# breakout_ina169.net
KiCad netlist of a schematic drawn in EAGLE
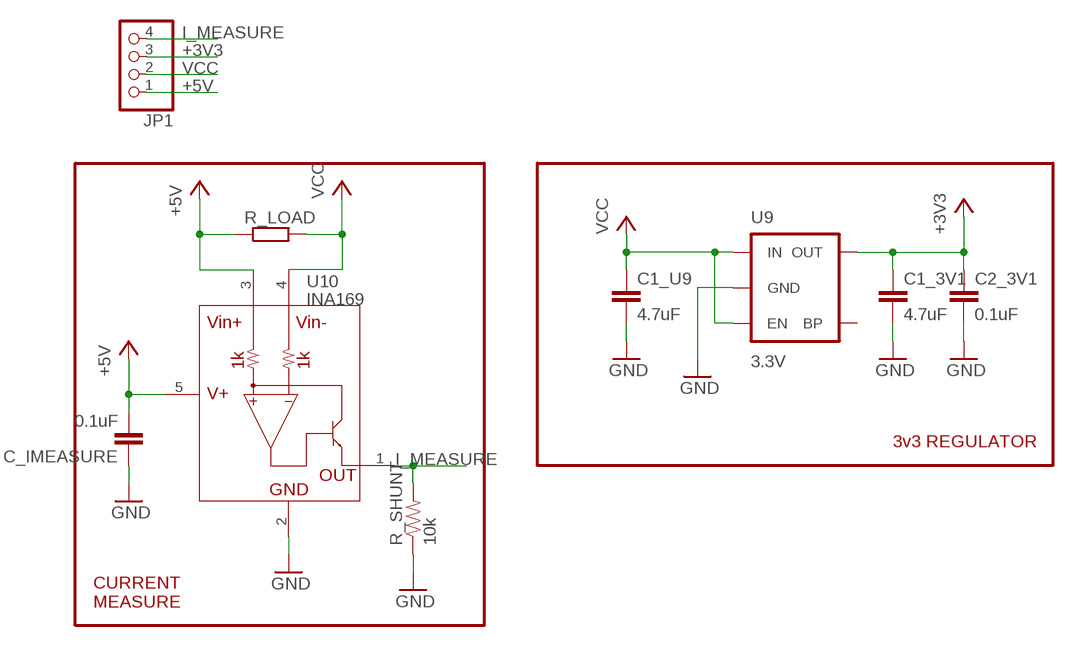
[diagram p0: schematic, sheet 1]

(export (version "E")
  (design (tool "Eeschema 10.0.6"))
  (components
    (comp (ref "C1_3V1")
      (value "4.7uF")
      (footprint "eagle-import:0402-CAP")
      (libsource (lib "eagle-import") (part "CAP0402-CAP"))
    )
    (comp (ref "C1_U9")
      (value "4.7uF")
      (footprint "eagle-import:0402-CAP")
      (libsource (lib "eagle-import") (part "CAP0402-CAP"))
    )
    (comp (ref "C2_3V1")
      (value "0.1uF")
      (footprint "eagle-import:0402-CAP")
      (libsource (lib "eagle-import") (part "CAP0402-CAP"))
    )
    (comp (ref "C_IMEASURE")
      (value "0.1uF")
      (footprint "eagle-import:0603-CAP")
      (libsource (lib "eagle-import") (part "SparkFun-Passives_CAP0603-CAP"))
    )
    (comp (ref "JP1")
      (value "PINHD-1X4")
      (footprint "eagle-import:1X04")
      (libsource (lib "eagle-import") (part "PINHD-1X4"))
    )
    (comp (ref "R_LOAD")
      (value "R-EU_0309/10")
      (footprint "eagle-import:0309_10")
      (fields (field (name "SIZE") "1206") (field (name "TOL") "1%"))
      (libsource (lib "eagle-import") (part "R-EU_0309/10"))
    )
    (comp (ref "R_SHUNT")
      (value "10k")
      (footprint "eagle-import:0603-RES")
      (fields (field (name "TOL") "1%"))
      (libsource (lib "eagle-import") (part "RESISTOR0603"))
    )
    (comp (ref "U9")
      (value "3.3V")
      (footprint "eagle-import:SOT23-5")
      (libsource (lib "eagle-import") (part "V_REG_LDOSMD"))
    )
    (comp (ref "U10")
      (value "INA169")
      (footprint "eagle-import:SOT23-5")
      (libsource (lib "eagle-import") (part "INA169"))
    )
  )
  (nets
    (net (code "1") (name "+3V3") (class "Default")
      (node (ref "C1_3V1") (pin "1") (pinfunction "1_1") (pintype "passive"))
      (node (ref "C2_3V1") (pin "1") (pinfunction "1_1") (pintype "passive"))
      (node (ref "JP1") (pin "3") (pinfunction "3_3") (pintype "passive"))
      (node (ref "U9") (pin "5") (pinfunction "OUT_5") (pintype "passive"))
    )
    (net (code "2") (name "+5V") (class "Default")
      (node (ref "C_IMEASURE") (pin "2") (pinfunction "2_2") (pintype "passive"))
      (node (ref "JP1") (pin "1") (pinfunction "1_1") (pintype "passive"))
      (node (ref "R_LOAD") (pin "1") (pinfunction "1_1") (pintype "passive"))
      (node (ref "U10") (pin "3") (pinfunction "VIN+_3") (pintype "bidirectional"))
      (node (ref "U10") (pin "5") (pinfunction "V+_5") (pintype "bidirectional"))
    )
    (net (code "3") (name "/I_MEASURE") (class "Default")
      (node (ref "JP1") (pin "4") (pinfunction "4_4") (pintype "passive"))
      (node (ref "R_SHUNT") (pin "2") (pinfunction "2_2") (pintype "passive"))
      (node (ref "U10") (pin "1") (pinfunction "OUT_1") (pintype "bidirectional"))
    )
    (net (code "4") (name "GND") (class "Default")
      (node (ref "C1_3V1") (pin "2") (pinfunction "2_2") (pintype "passive"))
      (node (ref "C1_U9") (pin "2") (pinfunction "2_2") (pintype "passive"))
      (node (ref "C2_3V1") (pin "2") (pinfunction "2_2") (pintype "passive"))
      (node (ref "C_IMEASURE") (pin "1") (pinfunction "1_1") (pintype "passive"))
      (node (ref "R_SHUNT") (pin "1") (pinfunction "1_1") (pintype "passive"))
      (node (ref "U10") (pin "2") (pinfunction "GND_2") (pintype "bidirectional"))
      (node (ref "U9") (pin "2") (pinfunction "GND_2") (pintype "input"))
    )
    (net (code "5") (name "VCC") (class "Default")
      (node (ref "C1_U9") (pin "1") (pinfunction "1_1") (pintype "passive"))
      (node (ref "JP1") (pin "2") (pinfunction "2_2") (pintype "passive"))
      (node (ref "R_LOAD") (pin "2") (pinfunction "2_2") (pintype "passive"))
      (node (ref "U10") (pin "4") (pinfunction "VIN-_4") (pintype "bidirectional"))
      (node (ref "U9") (pin "1") (pinfunction "IN_1") (pintype "input"))
      (node (ref "U9") (pin "3") (pinfunction "EN_3") (pintype "input"))
    )
    (net (code "6") (name "unconnected-(U9-BP-Pad4)") (class "Default")
      (node (ref "U9") (pin "4") (pinfunction "BP_4") (pintype "input"))
    )
  )
)
